# start.net
KiCad netlist of a schematic drawn in EAGLE
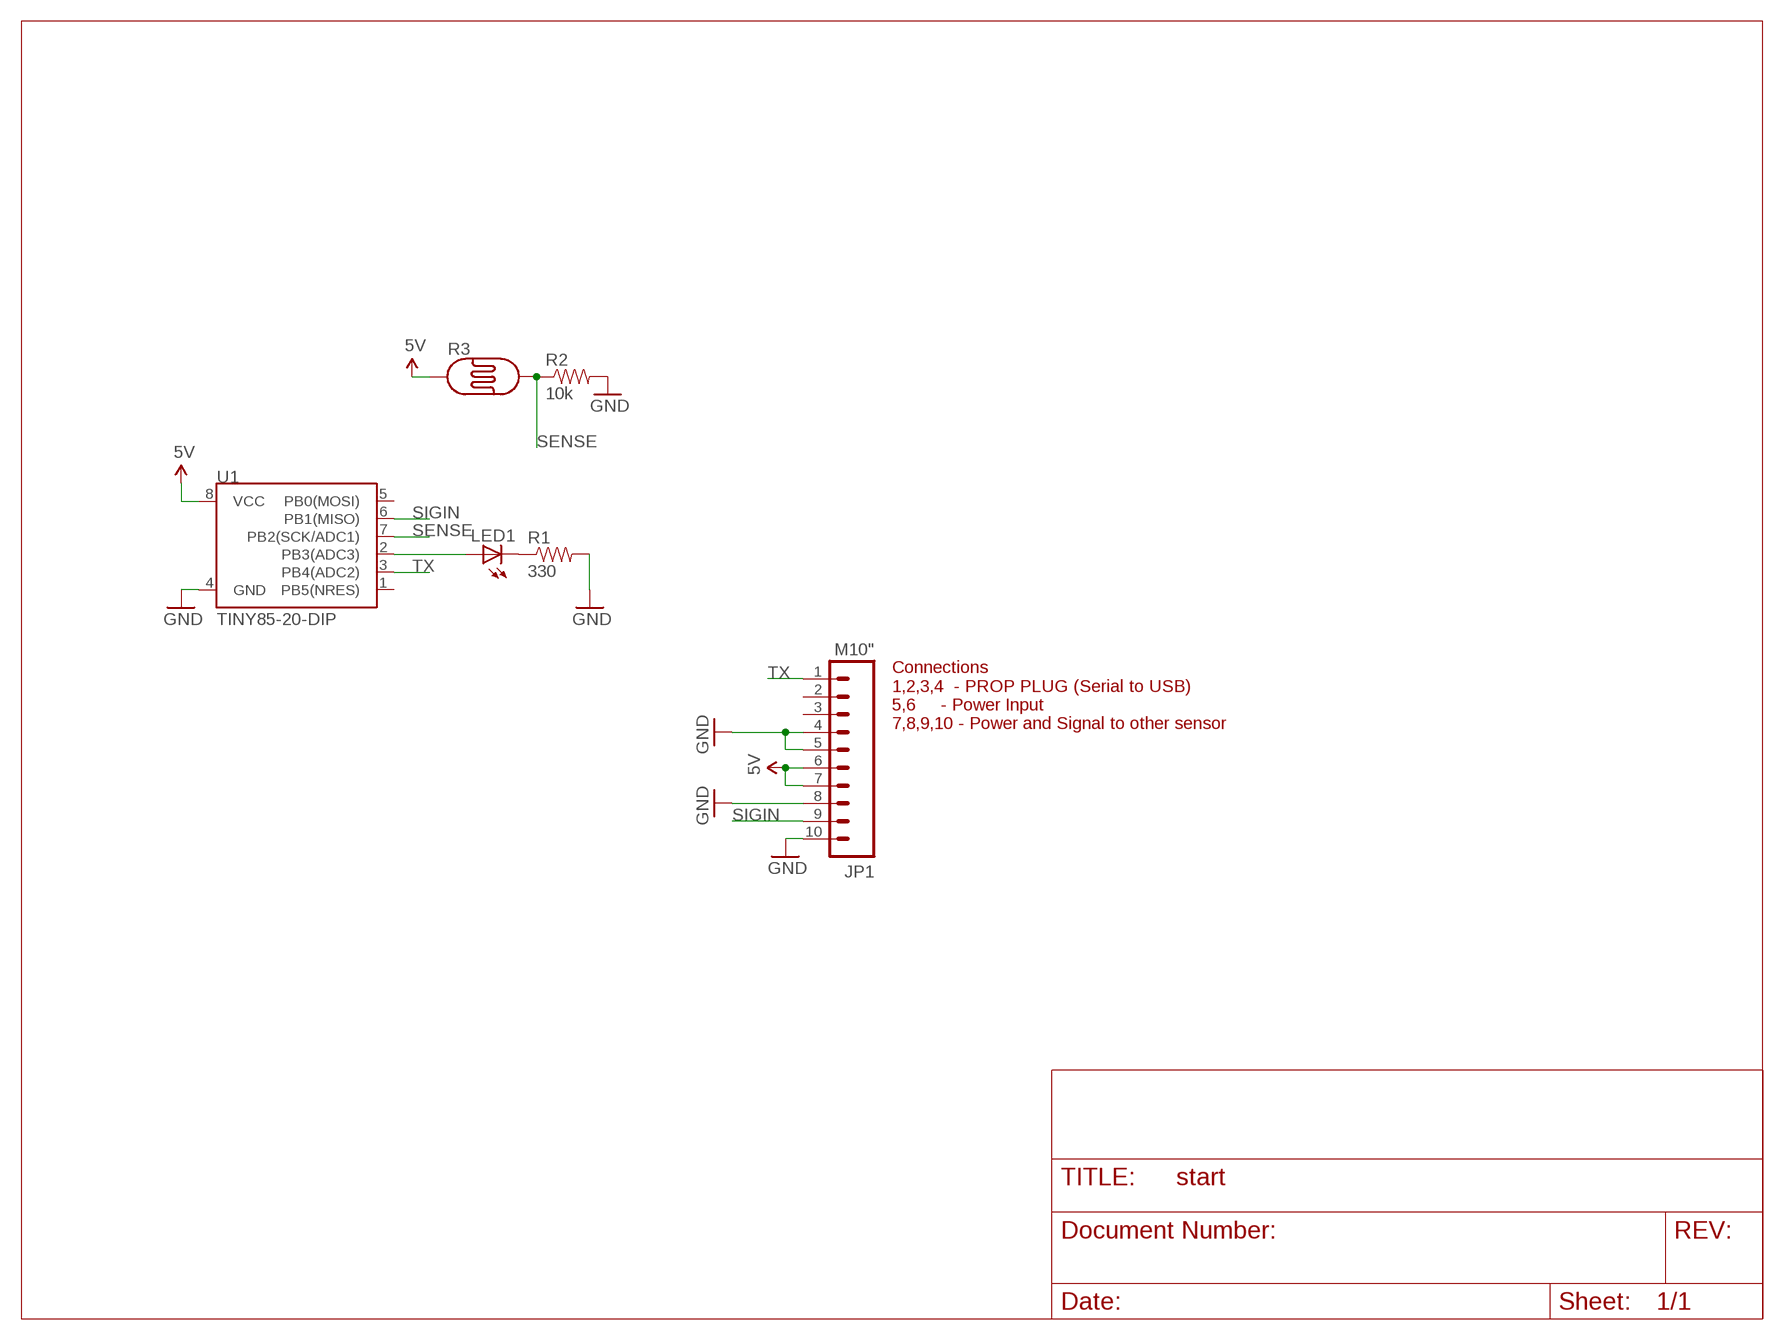
[diagram p0: schematic, sheet 1]

(export (version "E")
  (design (tool "Eeschema 10.0.6"))
  (components
    (comp (ref "JP1")
      (value "M10\"")
      (footprint "eagle-import:1X10")
      (libsource (lib "eagle-import") (part "M10{dblquote}"))
    )
    (comp (ref "LED1")
      (value "LED5MM")
      (footprint "eagle-import:LED5MM")
      (libsource (lib "eagle-import") (part "LED5MM"))
    )
    (comp (ref "R1")
      (value "330")
      (footprint "eagle-import:AXIAL-0.4")
      (libsource (lib "eagle-import") (part "RESISTORPTH-1/4W"))
    )
    (comp (ref "R2")
      (value "10k")
      (footprint "eagle-import:AXIAL-0.4")
      (libsource (lib "eagle-import") (part "RESISTORPTH-1/4W"))
    )
    (comp (ref "R3")
      (value "PHOTOCELLPTH")
      (footprint "eagle-import:PHOTOCELL")
      (libsource (lib "eagle-import") (part "PHOTOCELLPTH"))
    )
    (comp (ref "U1")
      (value "TINY85-20-DIP")
      (footprint "eagle-import:DIP08")
      (libsource (lib "eagle-import") (part "ATTINY45TINY85-20-DIP"))
    )
  )
  (nets
    (net (code "1") (name "/SENSE") (class "Default")
      (node (ref "R2") (pin "P$1") (pinfunction "1_P$1") (pintype "passive"))
      (node (ref "R3") (pin "2") (pinfunction "P$2_2") (pintype "bidirectional"))
      (node (ref "U1") (pin "7") (pinfunction "PB2(SCK/ADC1)_7") (pintype "bidirectional"))
    )
    (net (code "2") (name "/SIGIN") (class "Default")
      (node (ref "JP1") (pin "9") (pinfunction "9_9") (pintype "passive"))
      (node (ref "U1") (pin "6") (pinfunction "PB1(MISO)_6") (pintype "bidirectional"))
    )
    (net (code "3") (name "/TX") (class "Default")
      (node (ref "JP1") (pin "1") (pinfunction "1_1") (pintype "passive"))
      (node (ref "U1") (pin "3") (pinfunction "PB4(ADC2)_3") (pintype "bidirectional"))
    )
    (net (code "4") (name "5V") (class "Default")
      (node (ref "JP1") (pin "6") (pinfunction "6_6") (pintype "passive"))
      (node (ref "JP1") (pin "7") (pinfunction "7_7") (pintype "passive"))
      (node (ref "R3") (pin "1") (pinfunction "P$1_1") (pintype "bidirectional"))
      (node (ref "U1") (pin "8") (pinfunction "VCC_8") (pintype "bidirectional"))
    )
    (net (code "5") (name "GND") (class "Default")
      (node (ref "JP1") (pin "10") (pinfunction "10_10") (pintype "passive"))
      (node (ref "JP1") (pin "4") (pinfunction "4_4") (pintype "passive"))
      (node (ref "JP1") (pin "5") (pinfunction "5_5") (pintype "passive"))
      (node (ref "JP1") (pin "8") (pinfunction "8_8") (pintype "passive"))
      (node (ref "R1") (pin "P$2") (pinfunction "2_P$2") (pintype "passive"))
      (node (ref "R2") (pin "P$2") (pinfunction "2_P$2") (pintype "passive"))
      (node (ref "U1") (pin "4") (pinfunction "GND_4") (pintype "bidirectional"))
    )
    (net (code "6") (name "Net-(LED1-C)") (class "Default")
      (node (ref "LED1") (pin "K") (pinfunction "C_K") (pintype "passive"))
      (node (ref "R1") (pin "P$1") (pinfunction "1_P$1") (pintype "passive"))
    )
    (net (code "7") (name "Net-(U1-PB3(ADC3))") (class "Default")
      (node (ref "LED1") (pin "A") (pinfunction "A_A") (pintype "passive"))
      (node (ref "U1") (pin "2") (pinfunction "PB3(ADC3)_2") (pintype "bidirectional"))
    )
    (net (code "8") (name "unconnected-(JP1-Pad2)") (class "Default")
      (node (ref "JP1") (pin "2") (pinfunction "2_2") (pintype "passive"))
    )
    (net (code "9") (name "unconnected-(JP1-Pad3)") (class "Default")
      (node (ref "JP1") (pin "3") (pinfunction "3_3") (pintype "passive"))
    )
    (net (code "10") (name "unconnected-(U1-PB0(MOSI)-Pad5)") (class "Default")
      (node (ref "U1") (pin "5") (pinfunction "PB0(MOSI)_5") (pintype "bidirectional"))
    )
    (net (code "11") (name "unconnected-(U1-PB5(NRES)-Pad1)") (class "Default")
      (node (ref "U1") (pin "1") (pinfunction "PB5(NRES)_1") (pintype "bidirectional"))
    )
  )
)
